# ADC_SSR.net
KiCad netlist of a schematic drawn in Altium Designer
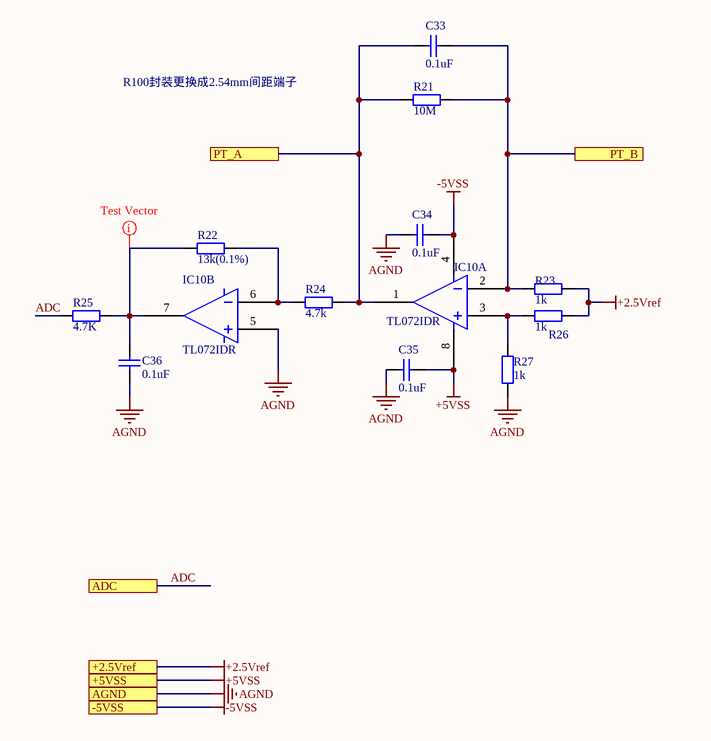
[diagram p0: ADC&SSR.SchDoc]

(export (version "E")
  (design (tool "Eeschema 10.0.6"))
  (components
    (comp (ref "C33")
      (value "0.1uF")
      (footprint "0805C")
      (description "品牌： SAMSUNG(三星)   型号： CL21C101JBANNNC   容值：100pF 精度：±5% 额定电压：50V 材质(温度系数)：C0G 材质:C0G")
      (fields (field (name "PUBLISHER") "Altium Limited"))
      (libsource (lib "Miscellaneous Devices") (part "Cap"))
    )
    (comp (ref "C34")
      (value "0.1uF")
      (footprint "0805C")
      (description "品牌： SAMSUNG(三星) 型号： CL21B104KBCNNNC ：容值：100nF 精度：±10% 额定电压：50V 材质(温度系数)：X7R 材质:X7R")
      (fields (field (name "PUBLISHER") "Altium Limited"))
      (libsource (lib "Miscellaneous Devices") (part "Cap"))
    )
    (comp (ref "C35")
      (value "0.1uF")
      (footprint "0805C")
      (description "品牌： SAMSUNG(三星) 型号： CL21B104KBCNNNC ：容值：100nF 精度：±10% 额定电压：50V 材质(温度系数)：X7R 材质:X7R")
      (fields (field (name "PUBLISHER") "Altium Limited"))
      (libsource (lib "Miscellaneous Devices") (part "Cap"))
    )
    (comp (ref "C36")
      (value "0.1uF")
      (footprint "0805C")
      (description "品牌： SAMSUNG(三星) 型号： CL21B104KBCNNNC ：容值：100nF 精度：±10% 额定电压：50V 材质(温度系数)：X7R 材质:X7R")
      (fields (field (name "PUBLISHER") "Altium Limited"))
      (libsource (lib "Miscellaneous Devices") (part "Cap"))
    )
    (comp (ref "IC10")
      (value "TL072IDR")
      (footprint "SOP8")
      (libsource (lib "main board fo stk_1") (part "TL072_1"))
    )
    (comp (ref "R21")
      (value "10M")
      (footprint "0805R")
      (fields (field (name "PUBLISHER") "Altium Limited"))
      (libsource (lib "") (part "Res2_1"))
    )
    (comp (ref "R22")
      (value "13k(0.1%)")
      (footprint "0805R")
      (description "品牌： UNI-ROYAL(厚声)  型号： 0805W8F1302T5E  电阻类型：厚膜电阻 阻值：13kΩ 精度：±1% 功率：125mW 温度系数：±100ppm/℃")
      (fields (field (name "PUBLISHER") "Altium Limited"))
      (libsource (lib "Miscellaneous Devices") (part "Res2"))
    )
    (comp (ref "R23")
      (value "1k")
      (footprint "0805R")
      (description "品牌： UNI-ROYAL(厚声) 型号： 0805W8F1001T5E 电阻类型：厚膜电阻 阻值：1kΩ 精度：±1% 功率：125mW 温度系数：±100ppm/℃")
      (fields (field (name "PUBLISHER") "Altium Limited"))
      (libsource (lib "Miscellaneous Devices") (part "Res2"))
    )
    (comp (ref "R24")
      (value "4.7k")
      (footprint "0805R")
      (description "品牌： UNI-ROYAL(厚声) 型号： 0805W8F4701T5E 电阻类型：厚膜电阻 阻值：4.7kΩ 精度：±1% 功率：125mW 温度系数：±100ppm/℃")
      (fields (field (name "PUBLISHER") "Altium Limited"))
      (libsource (lib "Miscellaneous Devices") (part "Res2"))
    )
    (comp (ref "R25")
      (value "4.7K")
      (footprint "0805R")
      (description "品牌： UNI-ROYAL(厚声) 型号： 0805W8F4701T5E 电阻类型：厚膜电阻 阻值：4.7kΩ 精度：±1% 功率：125mW 温度系数：±100ppm/℃")
      (fields (field (name "PUBLISHER") "Altium Limited"))
      (libsource (lib "Miscellaneous Devices") (part "Res2"))
    )
    (comp (ref "R26")
      (value "1k")
      (footprint "0805R")
      (description "品牌： UNI-ROYAL(厚声) 型号： 0805W8F1001T5E 电阻类型：厚膜电阻 阻值：1kΩ 精度：±1% 功率：125mW 温度系数：±100ppm/℃")
      (fields (field (name "PUBLISHER") "Altium Limited"))
      (libsource (lib "Miscellaneous Devices") (part "Res2"))
    )
    (comp (ref "R27")
      (value "1k")
      (footprint "0805R")
      (description "品牌： UNI-ROYAL(厚声) 型号： 0805W8F1001T5E 电阻类型：厚膜电阻 阻值：1kΩ 精度：±1% 功率：125mW 温度系数：±100ppm/℃")
      (fields (field (name "PUBLISHER") "Altium Limited"))
      (libsource (lib "") (part "Res2_2"))
    )
  )
  (nets
    (net (code "1") (name "+2.5Vref") (class "Default")
      (node (ref "R23") (pin "1") (pinfunction "1_1") (pintype "passive"))
      (node (ref "R26") (pin "1") (pinfunction "1_1") (pintype "passive"))
    )
    (net (code "2") (name "+5VSS") (class "Default")
      (node (ref "C35") (pin "2") (pinfunction "2_2") (pintype "passive"))
      (node (ref "IC10") (pin "8") (pintype "passive"))
    )
    (net (code "3") (name "-5VSS") (class "Default")
      (node (ref "C34") (pin "2") (pinfunction "2_2") (pintype "passive"))
      (node (ref "IC10") (pin "4") (pintype "passive"))
    )
    (net (code "5") (name "/ADC") (class "Default")
      (node (ref "R25") (pin "2") (pinfunction "2_2") (pintype "passive"))
    )
    (net (code "6") (name "/PT_A") (class "Default")
      (node (ref "C33") (pin "1") (pinfunction "1_1") (pintype "passive"))
      (node (ref "IC10") (pin "1") (pintype "passive"))
      (node (ref "R21") (pin "1") (pinfunction "1_1") (pintype "passive"))
      (node (ref "R24") (pin "1") (pinfunction "1_1") (pintype "passive"))
    )
    (net (code "7") (name "/PT_B") (class "Default")
      (node (ref "C33") (pin "2") (pinfunction "2_2") (pintype "passive"))
      (node (ref "IC10") (pin "2") (pintype "passive"))
      (node (ref "R21") (pin "2") (pinfunction "2_2") (pintype "passive"))
      (node (ref "R23") (pin "2") (pinfunction "2_2") (pintype "passive"))
    )
    (net (code "8") (name "AGND") (class "Default")
      (node (ref "C34") (pin "1") (pinfunction "1_1") (pintype "passive"))
      (node (ref "C35") (pin "1") (pinfunction "1_1") (pintype "passive"))
      (node (ref "C36") (pin "1") (pinfunction "1_1") (pintype "passive"))
      (node (ref "IC10") (pin "5") (pintype "passive"))
      (node (ref "R27") (pin "2") (pinfunction "2_2") (pintype "passive"))
    )
    (net (code "9") (name "Net-(C36-Pad2)") (class "Default")
      (node (ref "C36") (pin "2") (pinfunction "2_2") (pintype "passive"))
      (node (ref "IC10") (pin "7") (pintype "passive"))
      (node (ref "R22") (pin "2") (pinfunction "2_2") (pintype "passive"))
      (node (ref "R25") (pin "1") (pinfunction "1_1") (pintype "passive"))
    )
    (net (code "10") (name "Net-(IC10-Pad3)") (class "Default")
      (node (ref "IC10") (pin "3") (pintype "passive"))
      (node (ref "R26") (pin "2") (pinfunction "2_2") (pintype "passive"))
      (node (ref "R27") (pin "1") (pinfunction "1_1") (pintype "passive"))
    )
    (net (code "11") (name "Net-(IC10-Pad6)") (class "Default")
      (node (ref "IC10") (pin "6") (pintype "passive"))
      (node (ref "R22") (pin "1") (pinfunction "1_1") (pintype "passive"))
      (node (ref "R24") (pin "2") (pinfunction "2_2") (pintype "passive"))
    )
  )
)
